# rfid.net
KiCad netlist of a schematic drawn in Altium Designer
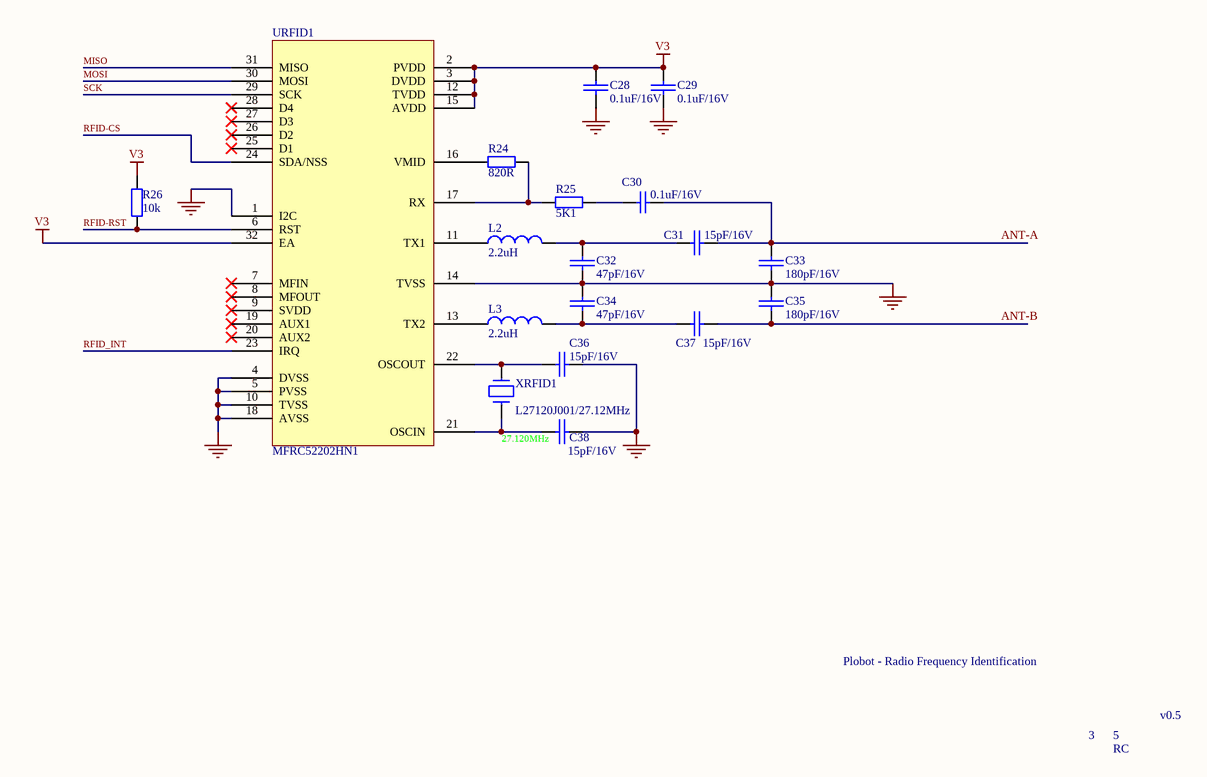
[diagram p0: rfid.SchDoc]

(export (version "E")
  (design (tool "Eeschema 10.0.6"))
  (components
    (comp (ref "C28")
      (value "0.1uF/16V")
      (footprint "CAPC1608N")
      (description "Capacitor")
      (libsource (lib "*") (part "Cap"))
    )
    (comp (ref "C29")
      (value "0.1uF/16V")
      (footprint "CAPC1608N")
      (description "Capacitor")
      (libsource (lib "*") (part "Cap"))
    )
    (comp (ref "C30")
      (value "0.1uF/16V")
      (footprint "CAPC1608N")
      (description "Capacitor")
      (fields (field (name "PUBLISHER") "Altium Limited"))
      (libsource (lib "") (part "Cap_1"))
    )
    (comp (ref "C31")
      (value "15pF/16V")
      (footprint "CAPC1608N")
      (description "Capacitor")
      (libsource (lib "*") (part "Cap"))
    )
    (comp (ref "C32")
      (value "47pF/16V")
      (footprint "CAPC1608N")
      (description "Capacitor")
      (libsource (lib "*") (part "Cap"))
    )
    (comp (ref "C33")
      (value "180pF/16V")
      (footprint "CAPC1608N")
      (description "Capacitor")
      (libsource (lib "*") (part "Cap"))
    )
    (comp (ref "C34")
      (value "47pF/16V")
      (footprint "CAPC1608N")
      (description "Capacitor")
      (libsource (lib "*") (part "Cap"))
    )
    (comp (ref "C35")
      (value "180pF/16V")
      (footprint "CAPC1608N")
      (description "Capacitor")
      (libsource (lib "*") (part "Cap"))
    )
    (comp (ref "C36")
      (value "15pF/16V")
      (footprint "CAPC1608N")
      (description "Capacitor")
      (libsource (lib "*") (part "CAP"))
    )
    (comp (ref "C37")
      (value "15pF/16V")
      (footprint "CAPC1608N")
      (description "Capacitor")
      (libsource (lib "*") (part "Cap"))
    )
    (comp (ref "C38")
      (value "15pF/16V")
      (footprint "CAPC1608N")
      (description "Capacitor")
      (libsource (lib "*") (part "CAP"))
    )
    (comp (ref "L2")
      (value "2.2uH")
      (footprint "INDC1608N")
      (description "Inductor")
      (fields (field (name "PUBLISHER") "Altium Limited"))
      (libsource (lib "Miscellaneous Devices") (part "Inductor"))
    )
    (comp (ref "L3")
      (value "2.2uH")
      (footprint "INDC1608N")
      (description "Inductor")
      (fields (field (name "PUBLISHER") "Altium Limited"))
      (libsource (lib "Miscellaneous Devices") (part "Inductor"))
    )
    (comp (ref "R24")
      (value "820R")
      (footprint "plobot_review:RESC1608N")
      (description "Resistor")
      (fields (field (name "PUBLISHER") "Altium Limited"))
      (libsource (lib "") (part "Res2_1"))
    )
    (comp (ref "R25")
      (value "5K1")
      (footprint "plobot_review:RESC1608N")
      (description "Resistor")
      (fields (field (name "PUBLISHER") "Altium Limited"))
      (libsource (lib "") (part "Res2_1"))
    )
    (comp (ref "R26")
      (value "10k")
      (footprint "plobot_review:RESC1608N")
      (description "Resistor")
      (fields (field (name "PUBLISHER") "Altium Limited"))
      (libsource (lib "*") (part "Res2"))
    )
    (comp (ref "URFID1")
      (value "MFRC52202HN1")
      (footprint "plobot_review:MFRC52202HN1")
      (libsource (lib "components") (part "MFRC52202HN1"))
    )
    (comp (ref "XRFID1")
      (value "L27120J001/27.12MHz")
      (footprint "XTAL")
      (libsource (lib "*") (part "Tm08B.S01_12M_42"))
    )
  )
  (nets
    (net (code "1") (name "/ANT-A") (class "Default")
      (node (ref "C30") (pin "2") (pinfunction "2_2") (pintype "passive"))
      (node (ref "C31") (pin "2") (pinfunction "2_2") (pintype "passive"))
      (node (ref "C33") (pin "2") (pinfunction "2_2") (pintype "passive"))
    )
    (net (code "2") (name "/ANT-B") (class "Default")
      (node (ref "C35") (pin "1") (pinfunction "1_1") (pintype "passive"))
      (node (ref "C37") (pin "2") (pinfunction "2_2") (pintype "passive"))
    )
    (net (code "3") (name "/MISO") (class "Default")
      (node (ref "URFID1") (pin "31") (pinfunction "MISO_31") (pintype "passive"))
    )
    (net (code "4") (name "/MOSI") (class "Default")
      (node (ref "URFID1") (pin "30") (pinfunction "MOSI_30") (pintype "passive"))
    )
    (net (code "5") (name "/RFID-CS") (class "Default")
      (node (ref "URFID1") (pin "24") (pinfunction "SDA/NSS_24") (pintype "passive"))
    )
    (net (code "6") (name "/RFID-RST") (class "Default")
      (node (ref "R26") (pin "2") (pinfunction "2_2") (pintype "passive"))
      (node (ref "URFID1") (pin "6") (pinfunction "RST_6") (pintype "passive"))
    )
    (net (code "7") (name "/RFID_INT") (class "Default")
      (node (ref "URFID1") (pin "23") (pinfunction "IRQ_23") (pintype "passive"))
    )
    (net (code "8") (name "/SCK") (class "Default")
      (node (ref "URFID1") (pin "29") (pinfunction "SCK_29") (pintype "passive"))
    )
    (net (code "9") (name "GND") (class "Default")
      (node (ref "C28") (pin "1") (pinfunction "1_1") (pintype "passive"))
      (node (ref "C29") (pin "1") (pinfunction "1_1") (pintype "passive"))
      (node (ref "C32") (pin "1") (pinfunction "1_1") (pintype "passive"))
      (node (ref "C33") (pin "1") (pinfunction "1_1") (pintype "passive"))
      (node (ref "C34") (pin "2") (pinfunction "2_2") (pintype "passive"))
      (node (ref "C35") (pin "2") (pinfunction "2_2") (pintype "passive"))
      (node (ref "C36") (pin "2") (pinfunction "2_2") (pintype "passive"))
      (node (ref "C38") (pin "2") (pinfunction "2_2") (pintype "passive"))
      (node (ref "URFID1") (pin "1") (pinfunction "I2C_1") (pintype "passive"))
      (node (ref "URFID1") (pin "10") (pinfunction "TVSS_10") (pintype "passive"))
      (node (ref "URFID1") (pin "14") (pinfunction "TVSS_14") (pintype "passive"))
      (node (ref "URFID1") (pin "18") (pinfunction "AVSS_18") (pintype "passive"))
      (node (ref "URFID1") (pin "4") (pinfunction "DVSS_4") (pintype "passive"))
      (node (ref "URFID1") (pin "5") (pinfunction "PVSS_5") (pintype "passive"))
    )
    (net (code "10") (name "Net-(C30-Pad1)") (class "Default")
      (node (ref "C30") (pin "1") (pinfunction "1_1") (pintype "passive"))
      (node (ref "R25") (pin "1") (pinfunction "1_1") (pintype "passive"))
    )
    (net (code "11") (name "Net-(C31-Pad1)") (class "Default")
      (node (ref "C31") (pin "1") (pinfunction "1_1") (pintype "passive"))
      (node (ref "C32") (pin "2") (pinfunction "2_2") (pintype "passive"))
      (node (ref "L2") (pin "2") (pinfunction "2_2") (pintype "passive"))
    )
    (net (code "12") (name "Net-(C34-Pad1)") (class "Default")
      (node (ref "C34") (pin "1") (pinfunction "1_1") (pintype "passive"))
      (node (ref "C37") (pin "1") (pinfunction "1_1") (pintype "passive"))
      (node (ref "L3") (pin "2") (pinfunction "2_2") (pintype "passive"))
    )
    (net (code "13") (name "Net-(URFID1-OSCIN)") (class "Default")
      (node (ref "C38") (pin "1") (pinfunction "1_1") (pintype "passive"))
      (node (ref "URFID1") (pin "21") (pinfunction "OSCIN_21") (pintype "passive"))
      (node (ref "XRFID1") (pin "1") (pintype "passive"))
    )
    (net (code "14") (name "Net-(URFID1-OSCOUT)") (class "Default")
      (node (ref "C36") (pin "1") (pinfunction "1_1") (pintype "passive"))
      (node (ref "URFID1") (pin "22") (pinfunction "OSCOUT_22") (pintype "passive"))
      (node (ref "XRFID1") (pin "2") (pintype "passive"))
    )
    (net (code "15") (name "Net-(URFID1-RX)") (class "Default")
      (node (ref "R24") (pin "1") (pinfunction "1_1") (pintype "passive"))
      (node (ref "R25") (pin "2") (pinfunction "2_2") (pintype "passive"))
      (node (ref "URFID1") (pin "17") (pinfunction "RX_17") (pintype "passive"))
    )
    (net (code "16") (name "Net-(URFID1-TX1)") (class "Default")
      (node (ref "L2") (pin "1") (pinfunction "1_1") (pintype "passive"))
      (node (ref "URFID1") (pin "11") (pinfunction "TX1_11") (pintype "passive"))
    )
    (net (code "17") (name "Net-(URFID1-TX2)") (class "Default")
      (node (ref "L3") (pin "1") (pinfunction "1_1") (pintype "passive"))
      (node (ref "URFID1") (pin "13") (pinfunction "TX2_13") (pintype "passive"))
    )
    (net (code "18") (name "Net-(URFID1-VMID)") (class "Default")
      (node (ref "R24") (pin "2") (pinfunction "2_2") (pintype "passive"))
      (node (ref "URFID1") (pin "16") (pinfunction "VMID_16") (pintype "passive"))
    )
    (net (code "19") (name "V3") (class "Default")
      (node (ref "C28") (pin "2") (pinfunction "2_2") (pintype "passive"))
      (node (ref "C29") (pin "2") (pinfunction "2_2") (pintype "passive"))
      (node (ref "R26") (pin "1") (pinfunction "1_1") (pintype "passive"))
      (node (ref "URFID1") (pin "12") (pinfunction "TVDD_12") (pintype "passive"))
      (node (ref "URFID1") (pin "15") (pinfunction "AVDD_15") (pintype "passive"))
      (node (ref "URFID1") (pin "2") (pinfunction "PVDD_2") (pintype "passive"))
      (node (ref "URFID1") (pin "3") (pinfunction "DVDD_3") (pintype "passive"))
      (node (ref "URFID1") (pin "32") (pinfunction "EA_32") (pintype "passive"))
    )
    (net (code "20") (name "unconnected-(URFID1-AUX1-Pad19)") (class "Default")
      (node (ref "URFID1") (pin "19") (pinfunction "AUX1_19") (pintype "passive+no_connect"))
    )
    (net (code "21") (name "unconnected-(URFID1-AUX2-Pad20)") (class "Default")
      (node (ref "URFID1") (pin "20") (pinfunction "AUX2_20") (pintype "passive+no_connect"))
    )
    (net (code "22") (name "unconnected-(URFID1-D1-Pad25)") (class "Default")
      (node (ref "URFID1") (pin "25") (pinfunction "D1_25") (pintype "passive+no_connect"))
    )
    (net (code "23") (name "unconnected-(URFID1-D2-Pad26)") (class "Default")
      (node (ref "URFID1") (pin "26") (pinfunction "D2_26") (pintype "passive+no_connect"))
    )
    (net (code "24") (name "unconnected-(URFID1-D3-Pad27)") (class "Default")
      (node (ref "URFID1") (pin "27") (pinfunction "D3_27") (pintype "passive+no_connect"))
    )
    (net (code "25") (name "unconnected-(URFID1-D4-Pad28)") (class "Default")
      (node (ref "URFID1") (pin "28") (pinfunction "D4_28") (pintype "passive+no_connect"))
    )
    (net (code "26") (name "unconnected-(URFID1-MFIN-Pad7)") (class "Default")
      (node (ref "URFID1") (pin "7") (pinfunction "MFIN_7") (pintype "passive+no_connect"))
    )
    (net (code "27") (name "unconnected-(URFID1-MFOUT-Pad8)") (class "Default")
      (node (ref "URFID1") (pin "8") (pinfunction "MFOUT_8") (pintype "passive+no_connect"))
    )
    (net (code "28") (name "unconnected-(URFID1-SVDD-Pad9)") (class "Default")
      (node (ref "URFID1") (pin "9") (pinfunction "SVDD_9") (pintype "passive+no_connect"))
    )
  )
)
